# dc_adapter.net
KiCad netlist of a schematic drawn in EAGLE
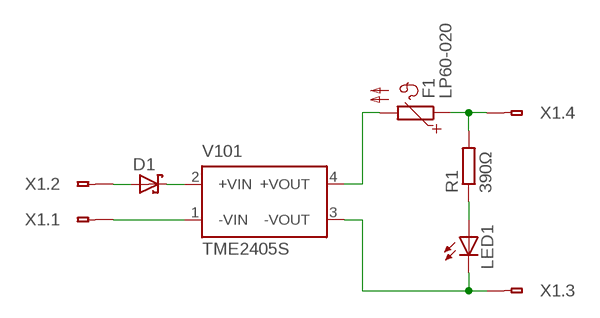
[diagram p0: schematic, sheet 1]

(export (version "E")
  (design (tool "Eeschema 10.0.6"))
  (components
    (comp (ref "D1")
      (value "SCHOTTKY-DIODEDO35-7")
      (footprint "eagle-import:DO35-7")
      (libsource (lib "eagle-import") (part "SCHOTTKY-DIODEDO35-7"))
    )
    (comp (ref "F1")
      (value "LP60-020")
      (footprint "eagle-import:LP60-020")
      (libsource (lib "eagle-import") (part "LP60-020"))
    )
    (comp (ref "LED1")
      (value "LED3MM")
      (footprint "eagle-import:LED3MM")
      (libsource (lib "eagle-import") (part "LED3MM"))
    )
    (comp (ref "R1")
      (value "390Ω")
      (footprint "eagle-import:0204V")
      (libsource (lib "eagle-import") (part "R_0204/2V"))
    )
    (comp (ref "V101")
      (value "TME2405S")
      (footprint "eagle-import:TME-24V")
      (fields
        (field (name "MPN") "TME 2405S")
        (field (name "MPN_1") "TME 2405S")
        (field (name "OC_FARNELL") "1007547")
        (field (name "OC_NEWARK") "51R5329")
      )
      (libsource (lib "eagle-import") (part "TME?2405S"))
    )
    (comp (ref "X1")
      (value "ST4")
      (footprint "eagle-import:STG4")
      (libsource (lib "eagle-import") (part "ST4"))
    )
  )
  (nets
    (net (code "1") (name "Net-(F1-1)") (class "Default")
      (node (ref "F1") (pin "P$1") (pinfunction "1_P$1") (pintype "passive"))
      (node (ref "R1") (pin "2") (pinfunction "2_2") (pintype "passive"))
      (node (ref "X1") (pin "4") (pinfunction "A_4") (pintype "passive"))
    )
    (net (code "2") (name "Net-(F1-2)") (class "Default")
      (node (ref "F1") (pin "P$2") (pinfunction "2_P$2") (pintype "passive"))
      (node (ref "V101") (pin "4") (pinfunction "+VOUT_4") (pintype "passive"))
    )
    (net (code "3") (name "Net-(LED1-C)") (class "Default")
      (node (ref "LED1") (pin "K") (pinfunction "C_K") (pintype "passive"))
      (node (ref "V101") (pin "3") (pinfunction "-VOUT_3") (pintype "passive"))
      (node (ref "X1") (pin "3") (pinfunction "A_3") (pintype "passive"))
    )
    (net (code "4") (name "Net-(LED1-PadA)") (class "Default")
      (node (ref "LED1") (pin "A") (pinfunction "A_A") (pintype "passive"))
      (node (ref "R1") (pin "1") (pinfunction "1_1") (pintype "passive"))
    )
    (net (code "5") (name "Net-(V101-+VIN)") (class "Default")
      (node (ref "D1") (pin "C") (pinfunction "C_C") (pintype "passive"))
      (node (ref "V101") (pin "2") (pinfunction "+VIN_2") (pintype "passive"))
    )
    (net (code "6") (name "Net-(V101--VIN)") (class "Default")
      (node (ref "V101") (pin "1") (pinfunction "-VIN_1") (pintype "passive"))
      (node (ref "X1") (pin "1") (pinfunction "A_1") (pintype "passive"))
    )
    (net (code "7") (name "Net-(X1B-A)") (class "Default")
      (node (ref "D1") (pin "A") (pinfunction "A_A") (pintype "passive"))
      (node (ref "X1") (pin "2") (pinfunction "A_2") (pintype "passive"))
    )
  )
)
